# MinSys.net
KiCad netlist of a schematic drawn in EAGLE
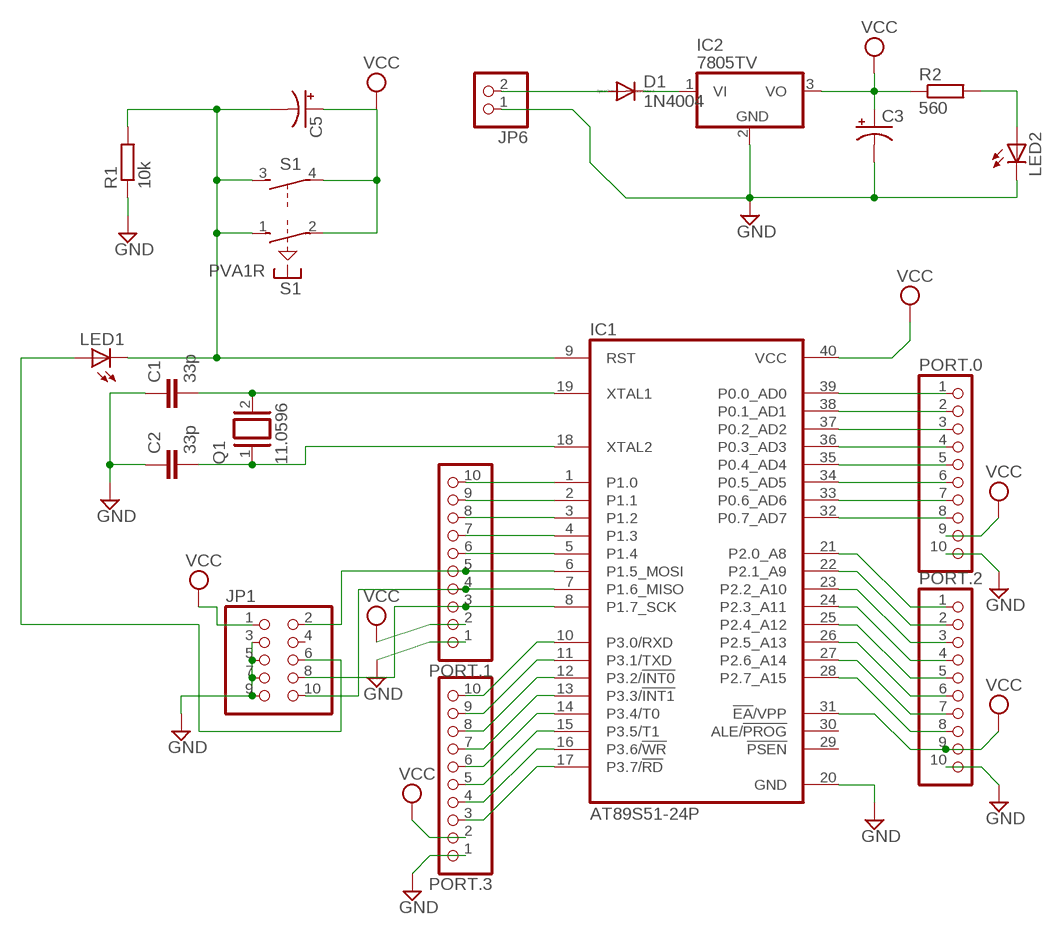
[diagram p0: schematic, sheet 1]

(export (version "E")
  (design (tool "Eeschema 10.0.6"))
  (components
    (comp (ref "C1")
      (value "33p")
      (footprint "eagle-import:C2.5-3")
      (libsource (lib "eagle-import") (part "C2,5-3"))
    )
    (comp (ref "C2")
      (value "33p")
      (footprint "eagle-import:C2.5-3")
      (libsource (lib "eagle-import") (part "C2,5-3"))
    )
    (comp (ref "C3")
      (value "CPOL-USE3.5-8")
      (footprint "eagle-import:E3,5-8")
      (libsource (lib "eagle-import") (part "CPOL-USE3.5-8"))
    )
    (comp (ref "C5")
      (value "CPOL-USE2.5-6")
      (footprint "eagle-import:E2,5-6")
      (libsource (lib "eagle-import") (part "CPOL-USE2.5-6"))
    )
    (comp (ref "D1")
      (value "1N4004")
      (footprint "eagle-import:DO41-10")
      (libsource (lib "eagle-import") (part "1N4004"))
    )
    (comp (ref "IC1")
      (value "AT89S51-24P")
      (footprint "eagle-import:DIL40")
      (fields (field (name "MPN") "AT89S51-24PU"))
      (libsource (lib "eagle-import") (part "AT89S51-P24"))
    )
    (comp (ref "IC2")
      (value "7805TV")
      (footprint "eagle-import:TO220V")
      (libsource (lib "eagle-import") (part "78TV05"))
    )
    (comp (ref "JP1")
      (value "PINHD-2X5")
      (footprint "eagle-import:2X05")
      (libsource (lib "eagle-import") (part "PINHD-2X5"))
    )
    (comp (ref "JP6")
      (value "PINHD-1X2")
      (footprint "eagle-import:1X02")
      (libsource (lib "eagle-import") (part "PINHD-1X2"))
    )
    (comp (ref "LED1")
      (value "LED3MM")
      (footprint "eagle-import:LED3MM")
      (libsource (lib "eagle-import") (part "LED3MM"))
    )
    (comp (ref "LED2")
      (value "LED3MM")
      (footprint "eagle-import:LED3MM")
      (libsource (lib "eagle-import") (part "LED3MM"))
    )
    (comp (ref "PORT.0")
      (value "PINHD-1X10")
      (footprint "eagle-import:1X10")
      (libsource (lib "eagle-import") (part "PINHD-1X10"))
    )
    (comp (ref "PORT.1")
      (value "PINHD-1X10")
      (footprint "eagle-import:1X10")
      (libsource (lib "eagle-import") (part "PINHD-1X10"))
    )
    (comp (ref "PORT.2")
      (value "PINHD-1X10")
      (footprint "eagle-import:1X10")
      (libsource (lib "eagle-import") (part "PINHD-1X10"))
    )
    (comp (ref "PORT.3")
      (value "PINHD-1X10")
      (footprint "eagle-import:1X10")
      (libsource (lib "eagle-import") (part "PINHD-1X10"))
    )
    (comp (ref "Q1")
      (value "11.0596")
      (footprint "eagle-import:QS")
      (libsource (lib "eagle-import") (part "XTAL/S"))
    )
    (comp (ref "R1")
      (value "10k")
      (footprint "eagle-import:0207_10")
      (libsource (lib "eagle-import") (part "R-EU_0207/10"))
    )
    (comp (ref "R2")
      (value "560")
      (footprint "eagle-import:0207_10")
      (libsource (lib "eagle-import") (part "resistor_R-EU_0207/10"))
    )
    (comp (ref "S1")
      (value "PVA1R")
      (footprint "eagle-import:PVA1R")
      (libsource (lib "eagle-import") (part "PVA1R"))
    )
  )
  (nets
    (net (code "1") (name "GND") (class "Default")
      (node (ref "C1") (pin "1") (pinfunction "1_1") (pintype "passive"))
      (node (ref "C2") (pin "1") (pinfunction "1_1") (pintype "passive"))
      (node (ref "C3") (pin "-") (pinfunction "-_-") (pintype "passive"))
      (node (ref "IC1") (pin "20") (pinfunction "GND_20") (pintype "power_in"))
      (node (ref "IC2") (pin "2") (pinfunction "GND_2") (pintype "passive"))
      (node (ref "JP1") (pin "3") (pinfunction "3_3") (pintype "passive"))
      (node (ref "JP1") (pin "5") (pinfunction "5_5") (pintype "passive"))
      (node (ref "JP1") (pin "7") (pinfunction "7_7") (pintype "passive"))
      (node (ref "JP1") (pin "9") (pinfunction "9_9") (pintype "passive"))
      (node (ref "JP6") (pin "1") (pinfunction "1_1") (pintype "passive"))
      (node (ref "LED2") (pin "K") (pinfunction "C_K") (pintype "passive"))
      (node (ref "PORT.0") (pin "10") (pinfunction "10_10") (pintype "passive"))
      (node (ref "PORT.1") (pin "1") (pinfunction "1_1") (pintype "passive"))
      (node (ref "PORT.2") (pin "10") (pinfunction "10_10") (pintype "passive"))
      (node (ref "PORT.3") (pin "1") (pinfunction "1_1") (pintype "passive"))
      (node (ref "R1") (pin "1") (pinfunction "1_1") (pintype "passive"))
    )
    (net (code "2") (name "Net-(D1-PadA)") (class "Default")
      (node (ref "D1") (pin "A") (pinfunction "A_A") (pintype "passive"))
      (node (ref "JP6") (pin "2") (pinfunction "2_2") (pintype "passive"))
    )
    (net (code "3") (name "Net-(IC1-P0.0_AD0)") (class "Default")
      (node (ref "IC1") (pin "39") (pinfunction "P0.0_AD0_39") (pintype "bidirectional"))
      (node (ref "PORT.0") (pin "1") (pinfunction "1_1") (pintype "passive"))
    )
    (net (code "4") (name "Net-(IC1-P0.1_AD1)") (class "Default")
      (node (ref "IC1") (pin "38") (pinfunction "P0.1_AD1_38") (pintype "bidirectional"))
      (node (ref "PORT.0") (pin "2") (pinfunction "2_2") (pintype "passive"))
    )
    (net (code "5") (name "Net-(IC1-P0.2_AD2)") (class "Default")
      (node (ref "IC1") (pin "37") (pinfunction "P0.2_AD2_37") (pintype "bidirectional"))
      (node (ref "PORT.0") (pin "3") (pinfunction "3_3") (pintype "passive"))
    )
    (net (code "6") (name "Net-(IC1-P0.3_AD3)") (class "Default")
      (node (ref "IC1") (pin "36") (pinfunction "P0.3_AD3_36") (pintype "bidirectional"))
      (node (ref "PORT.0") (pin "4") (pinfunction "4_4") (pintype "passive"))
    )
    (net (code "7") (name "Net-(IC1-P0.4_AD4)") (class "Default")
      (node (ref "IC1") (pin "35") (pinfunction "P0.4_AD4_35") (pintype "bidirectional"))
      (node (ref "PORT.0") (pin "5") (pinfunction "5_5") (pintype "passive"))
    )
    (net (code "8") (name "Net-(IC1-P0.5_AD5)") (class "Default")
      (node (ref "IC1") (pin "34") (pinfunction "P0.5_AD5_34") (pintype "bidirectional"))
      (node (ref "PORT.0") (pin "6") (pinfunction "6_6") (pintype "passive"))
    )
    (net (code "9") (name "Net-(IC1-P0.6_AD6)") (class "Default")
      (node (ref "IC1") (pin "33") (pinfunction "P0.6_AD6_33") (pintype "bidirectional"))
      (node (ref "PORT.0") (pin "7") (pinfunction "7_7") (pintype "passive"))
    )
    (net (code "10") (name "Net-(IC1-P0.7_AD7)") (class "Default")
      (node (ref "IC1") (pin "32") (pinfunction "P0.7_AD7_32") (pintype "bidirectional"))
      (node (ref "PORT.0") (pin "8") (pinfunction "8_8") (pintype "passive"))
    )
    (net (code "11") (name "Net-(IC1-P1.0)") (class "Default")
      (node (ref "IC1") (pin "1") (pinfunction "P1.0_1") (pintype "bidirectional"))
      (node (ref "PORT.1") (pin "10") (pinfunction "10_10") (pintype "passive"))
    )
    (net (code "12") (name "Net-(IC1-P1.1)") (class "Default")
      (node (ref "IC1") (pin "2") (pinfunction "P1.1_2") (pintype "bidirectional"))
      (node (ref "PORT.1") (pin "9") (pinfunction "9_9") (pintype "passive"))
    )
    (net (code "13") (name "Net-(IC1-P1.2)") (class "Default")
      (node (ref "IC1") (pin "3") (pinfunction "P1.2_3") (pintype "bidirectional"))
      (node (ref "PORT.1") (pin "8") (pinfunction "8_8") (pintype "passive"))
    )
    (net (code "14") (name "Net-(IC1-P1.3)") (class "Default")
      (node (ref "IC1") (pin "4") (pinfunction "P1.3_4") (pintype "bidirectional"))
      (node (ref "PORT.1") (pin "7") (pinfunction "7_7") (pintype "passive"))
    )
    (net (code "15") (name "Net-(IC1-P1.4)") (class "Default")
      (node (ref "IC1") (pin "5") (pinfunction "P1.4_5") (pintype "bidirectional"))
      (node (ref "PORT.1") (pin "6") (pinfunction "6_6") (pintype "passive"))
    )
    (net (code "16") (name "Net-(IC1-P1.5_MOSI)") (class "Default")
      (node (ref "IC1") (pin "6") (pinfunction "P1.5_MOSI_6") (pintype "bidirectional"))
      (node (ref "JP1") (pin "2") (pinfunction "2_2") (pintype "passive"))
      (node (ref "PORT.1") (pin "5") (pinfunction "5_5") (pintype "passive"))
    )
    (net (code "17") (name "Net-(IC1-P1.6_MISO)") (class "Default")
      (node (ref "IC1") (pin "7") (pinfunction "P1.6_MISO_7") (pintype "bidirectional"))
      (node (ref "JP1") (pin "10") (pinfunction "10_10") (pintype "passive"))
      (node (ref "PORT.1") (pin "4") (pinfunction "4_4") (pintype "passive"))
    )
    (net (code "18") (name "Net-(IC1-P1.7_SCK)") (class "Default")
      (node (ref "IC1") (pin "8") (pinfunction "P1.7_SCK_8") (pintype "bidirectional"))
      (node (ref "JP1") (pin "8") (pinfunction "8_8") (pintype "passive"))
      (node (ref "PORT.1") (pin "3") (pinfunction "3_3") (pintype "passive"))
    )
    (net (code "19") (name "Net-(IC1-P2.0_A8)") (class "Default")
      (node (ref "IC1") (pin "21") (pinfunction "P2.0_A8_21") (pintype "bidirectional"))
      (node (ref "PORT.2") (pin "1") (pinfunction "1_1") (pintype "passive"))
    )
    (net (code "20") (name "Net-(IC1-P2.1_A9)") (class "Default")
      (node (ref "IC1") (pin "22") (pinfunction "P2.1_A9_22") (pintype "bidirectional"))
      (node (ref "PORT.2") (pin "2") (pinfunction "2_2") (pintype "passive"))
    )
    (net (code "21") (name "Net-(IC1-P2.2_A10)") (class "Default")
      (node (ref "IC1") (pin "23") (pinfunction "P2.2_A10_23") (pintype "bidirectional"))
      (node (ref "PORT.2") (pin "3") (pinfunction "3_3") (pintype "passive"))
    )
    (net (code "22") (name "Net-(IC1-P2.3_A11)") (class "Default")
      (node (ref "IC1") (pin "24") (pinfunction "P2.3_A11_24") (pintype "bidirectional"))
      (node (ref "PORT.2") (pin "4") (pinfunction "4_4") (pintype "passive"))
    )
    (net (code "23") (name "Net-(IC1-P2.4_A12)") (class "Default")
      (node (ref "IC1") (pin "25") (pinfunction "P2.4_A12_25") (pintype "bidirectional"))
      (node (ref "PORT.2") (pin "5") (pinfunction "5_5") (pintype "passive"))
    )
    (net (code "24") (name "Net-(IC1-P2.5_A13)") (class "Default")
      (node (ref "IC1") (pin "26") (pinfunction "P2.5_A13_26") (pintype "bidirectional"))
      (node (ref "PORT.2") (pin "6") (pinfunction "6_6") (pintype "passive"))
    )
    (net (code "25") (name "Net-(IC1-P2.6_A14)") (class "Default")
      (node (ref "IC1") (pin "27") (pinfunction "P2.6_A14_27") (pintype "bidirectional"))
      (node (ref "PORT.2") (pin "7") (pinfunction "7_7") (pintype "passive"))
    )
    (net (code "26") (name "Net-(IC1-P2.7_A15)") (class "Default")
      (node (ref "IC1") (pin "28") (pinfunction "P2.7_A15_28") (pintype "bidirectional"))
      (node (ref "PORT.2") (pin "8") (pinfunction "8_8") (pintype "passive"))
    )
    (net (code "27") (name "Net-(IC1-P3.0{slash}RXD)") (class "Default")
      (node (ref "IC1") (pin "10") (pinfunction "P3.0/RXD_10") (pintype "bidirectional"))
      (node (ref "PORT.3") (pin "10") (pinfunction "10_10") (pintype "passive"))
    )
    (net (code "28") (name "Net-(IC1-P3.1{slash}TXD)") (class "Default")
      (node (ref "IC1") (pin "11") (pinfunction "P3.1/TXD_11") (pintype "bidirectional"))
      (node (ref "PORT.3") (pin "9") (pinfunction "9_9") (pintype "passive"))
    )
    (net (code "29") (name "Net-(IC1-P3.2{slash}~{INT0})") (class "Default")
      (node (ref "IC1") (pin "12") (pinfunction "P3.2/~{INT0}_12") (pintype "bidirectional"))
      (node (ref "PORT.3") (pin "8") (pinfunction "8_8") (pintype "passive"))
    )
    (net (code "30") (name "Net-(IC1-P3.3{slash}~{INT1})") (class "Default")
      (node (ref "IC1") (pin "13") (pinfunction "P3.3/~{INT1}_13") (pintype "bidirectional"))
      (node (ref "PORT.3") (pin "7") (pinfunction "7_7") (pintype "passive"))
    )
    (net (code "31") (name "Net-(IC1-P3.4{slash}T0)") (class "Default")
      (node (ref "IC1") (pin "14") (pinfunction "P3.4/T0_14") (pintype "bidirectional"))
      (node (ref "PORT.3") (pin "6") (pinfunction "6_6") (pintype "passive"))
    )
    (net (code "32") (name "Net-(IC1-P3.5{slash}T1)") (class "Default")
      (node (ref "IC1") (pin "15") (pinfunction "P3.5/T1_15") (pintype "bidirectional"))
      (node (ref "PORT.3") (pin "5") (pinfunction "5_5") (pintype "passive"))
    )
    (net (code "33") (name "Net-(IC1-P3.6{slash}~{WR})") (class "Default")
      (node (ref "IC1") (pin "16") (pinfunction "P3.6/~{WR}_16") (pintype "bidirectional"))
      (node (ref "PORT.3") (pin "4") (pinfunction "4_4") (pintype "passive"))
    )
    (net (code "34") (name "Net-(IC1-P3.7{slash}~{RD})") (class "Default")
      (node (ref "IC1") (pin "17") (pinfunction "P3.7/~{RD}_17") (pintype "bidirectional"))
      (node (ref "PORT.3") (pin "3") (pinfunction "3_3") (pintype "passive"))
    )
    (net (code "35") (name "Net-(IC1-RST)") (class "Default")
      (node (ref "C5") (pin "-") (pinfunction "-_-") (pintype "passive"))
      (node (ref "IC1") (pin "9") (pinfunction "RST_9") (pintype "input"))
      (node (ref "LED1") (pin "K") (pinfunction "C_K") (pintype "passive"))
      (node (ref "R1") (pin "2") (pinfunction "2_2") (pintype "passive"))
      (node (ref "S1") (pin "1") (pinfunction "S_1") (pintype "passive"))
      (node (ref "S1") (pin "3") (pinfunction "S_3") (pintype "passive"))
    )
    (net (code "36") (name "Net-(IC1-XTAL1)") (class "Default")
      (node (ref "C1") (pin "2") (pinfunction "2_2") (pintype "passive"))
      (node (ref "IC1") (pin "19") (pinfunction "XTAL1_19") (pintype "input"))
      (node (ref "Q1") (pin "2") (pinfunction "2_2") (pintype "passive"))
    )
    (net (code "37") (name "Net-(IC1-XTAL2)") (class "Default")
      (node (ref "C2") (pin "2") (pinfunction "2_2") (pintype "passive"))
      (node (ref "IC1") (pin "18") (pinfunction "XTAL2_18") (pintype "input"))
      (node (ref "Q1") (pin "1") (pinfunction "1_1") (pintype "passive"))
    )
    (net (code "38") (name "Net-(IC2-VI)") (class "Default")
      (node (ref "D1") (pin "C") (pinfunction "C_C") (pintype "passive"))
      (node (ref "IC2") (pin "1") (pinfunction "VI_1") (pintype "input"))
    )
    (net (code "39") (name "Net-(JP1-Pad6)") (class "Default")
      (node (ref "JP1") (pin "6") (pinfunction "6_6") (pintype "passive"))
      (node (ref "LED1") (pin "A") (pinfunction "A_A") (pintype "passive"))
    )
    (net (code "40") (name "Net-(LED2-PadA)") (class "Default")
      (node (ref "LED2") (pin "A") (pinfunction "A_A") (pintype "passive"))
      (node (ref "R2") (pin "2") (pinfunction "2_2") (pintype "passive"))
    )
    (net (code "41") (name "VCC") (class "Default")
      (node (ref "C3") (pin "+") (pinfunction "+_+") (pintype "passive"))
      (node (ref "C5") (pin "+") (pinfunction "+_+") (pintype "passive"))
      (node (ref "IC1") (pin "31") (pinfunction "~{EA}/VPP_31") (pintype "input"))
      (node (ref "IC1") (pin "40") (pinfunction "VCC_40") (pintype "power_in"))
      (node (ref "IC2") (pin "3") (pinfunction "VO_3") (pintype "passive"))
      (node (ref "JP1") (pin "1") (pinfunction "1_1") (pintype "passive"))
      (node (ref "PORT.0") (pin "9") (pinfunction "9_9") (pintype "passive"))
      (node (ref "PORT.1") (pin "2") (pinfunction "2_2") (pintype "passive"))
      (node (ref "PORT.2") (pin "9") (pinfunction "9_9") (pintype "passive"))
      (node (ref "PORT.3") (pin "2") (pinfunction "2_2") (pintype "passive"))
      (node (ref "R2") (pin "1") (pinfunction "1_1") (pintype "passive"))
      (node (ref "S1") (pin "2") (pinfunction "P_2") (pintype "passive"))
      (node (ref "S1") (pin "4") (pinfunction "P_4") (pintype "passive"))
    )
    (net (code "42") (name "unconnected-(IC1-ALE{slash}~{PROG}-Pad30)") (class "Default")
      (node (ref "IC1") (pin "30") (pinfunction "ALE/~{PROG}_30") (pintype "output"))
    )
    (net (code "43") (name "unconnected-(IC1-~{PSEN}-Pad29)") (class "Default")
      (node (ref "IC1") (pin "29") (pinfunction "~{PSEN}_29") (pintype "output"))
    )
    (net (code "44") (name "unconnected-(JP1-Pad4)") (class "Default")
      (node (ref "JP1") (pin "4") (pinfunction "4_4") (pintype "passive"))
    )
  )
)
